# 4-20mA_Converter.net
KiCad netlist of a schematic drawn in Altium Designer
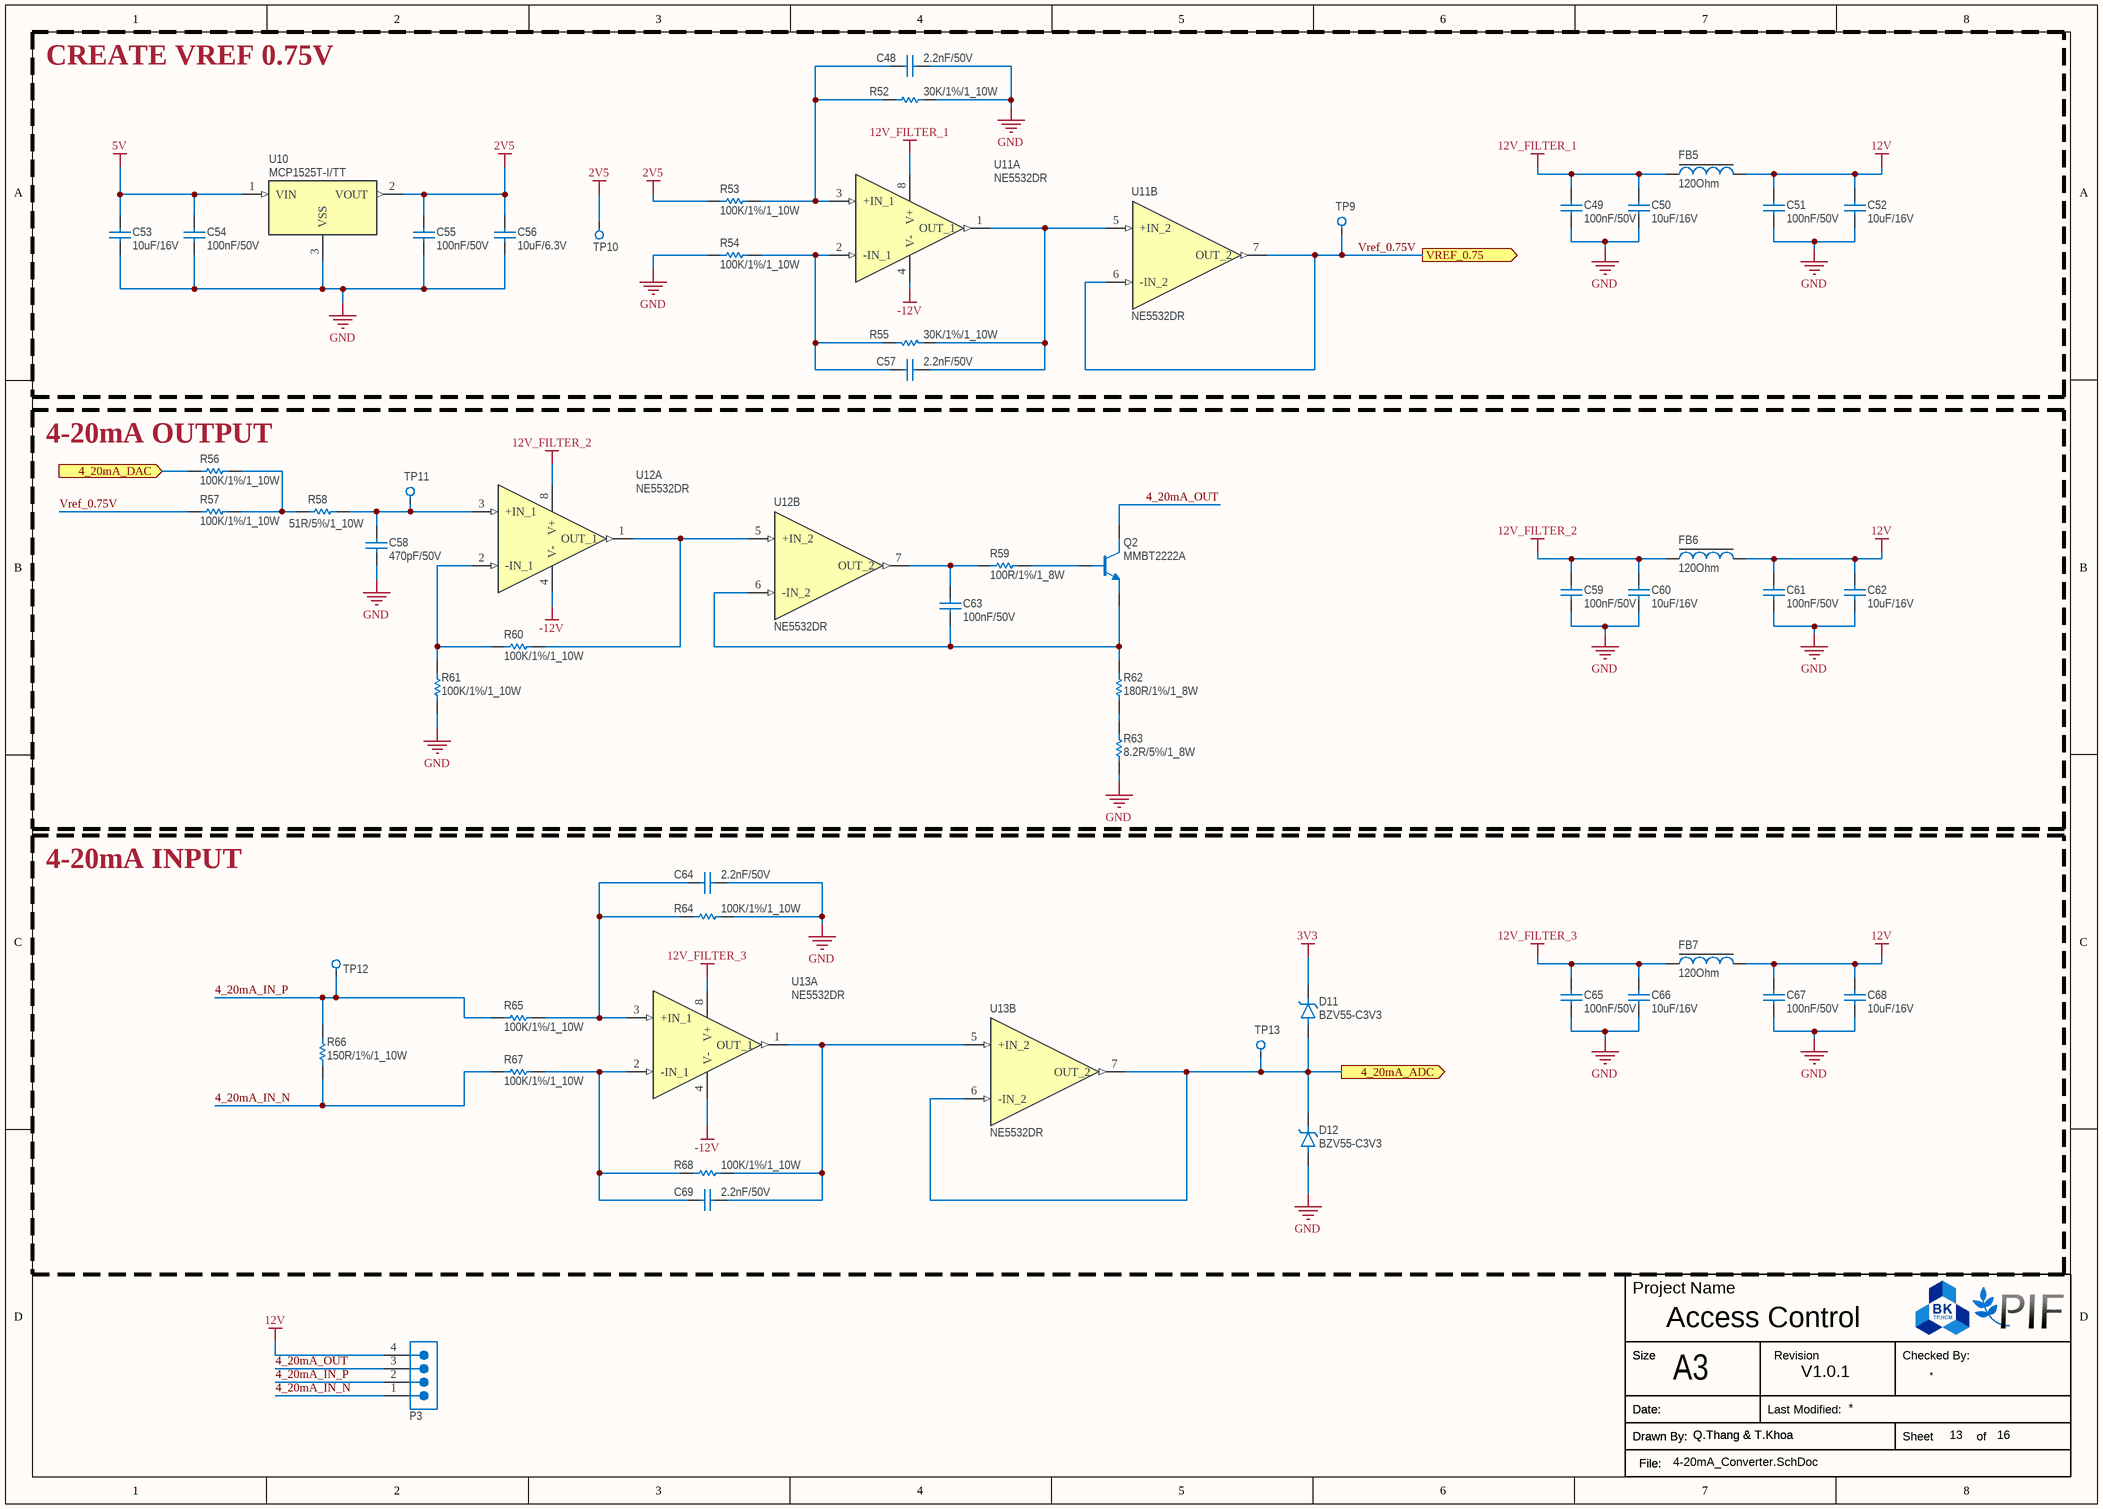
[diagram p0: 4-20mA_Converter.SchDoc]

(export (version "E")
  (design (tool "Eeschema 10.0.6"))
  (components
    (comp (ref "C48")
      (value "2.2nF/50V")
      (footprint "CAP_0603")
      (description "CAP, size 0603, 2.2nF, 50V")
      (fields (field (name "SUPPLY PART NUMBER") "CC0603KRX7R9BB222"))
      (libsource (lib "BluetoothTracking") (part "Ceramic_Cap_2.2nF_50V_0603"))
    )
    (comp (ref "C49")
      (value "100nF/50V")
      (footprint "CAP_0603")
      (description "CAP, size 0603, 100nF, 50V")
      (fields (field (name "SUPPLY PART NUMBER") "Tụ Gốm 0603 100nF (0.1uF) 50V"))
      (libsource (lib "BluetoothTracking") (part "Ceramic_Cap_100nF_50V_0603"))
    )
    (comp (ref "C50")
      (value "10uF/16V")
      (footprint "CAP_0603")
      (description "CAP, size 0603, 10uF, 16V")
      (fields (field (name "SUPPLY PART NUMBER") "Tụ Gốm 0603 10uF 16V"))
      (libsource (lib "BluetoothTracking") (part "Ceramic_Cap_10uF_16V_0603"))
    )
    (comp (ref "C51")
      (value "100nF/50V")
      (footprint "CAP_0603")
      (description "CAP, size 0603, 100nF, 50V")
      (fields (field (name "SUPPLY PART NUMBER") "Tụ Gốm 0603 100nF (0.1uF) 50V"))
      (libsource (lib "BluetoothTracking") (part "Ceramic_Cap_100nF_50V_0603"))
    )
    (comp (ref "C52")
      (value "10uF/16V")
      (footprint "CAP_0603")
      (description "CAP, size 0603, 10uF, 16V")
      (fields (field (name "SUPPLY PART NUMBER") "Tụ Gốm 0603 10uF 16V"))
      (libsource (lib "BluetoothTracking") (part "Ceramic_Cap_10uF_16V_0603"))
    )
    (comp (ref "C53")
      (value "10uF/16V")
      (footprint "CAP_0603")
      (description "CAP, size 0603, 10uF, 16V")
      (fields (field (name "SUPPLY PART NUMBER") "Tụ Gốm 0603 10uF 16V"))
      (libsource (lib "BluetoothTracking") (part "Ceramic_Cap_10uF_16V_0603"))
    )
    (comp (ref "C54")
      (value "100nF/50V")
      (footprint "CAP_0603")
      (description "CAP, size 0603, 100nF, 50V")
      (fields (field (name "SUPPLY PART NUMBER") "Tụ Gốm 0603 100nF (0.1uF) 50V"))
      (libsource (lib "BluetoothTracking") (part "Ceramic_Cap_100nF_50V_0603"))
    )
    (comp (ref "C55")
      (value "100nF/50V")
      (footprint "CAP_0603")
      (description "CAP, size 0603, 100nF, 50V")
      (fields (field (name "SUPPLY PART NUMBER") "Tụ Gốm 0603 100nF (0.1uF) 50V"))
      (libsource (lib "BluetoothTracking") (part "Ceramic_Cap_100nF_50V_0603"))
    )
    (comp (ref "C56")
      (value "10uF/6.3V")
      (footprint "CAP_0603")
      (description "CAP, size 0603, 10uF, 6.3V")
      (fields (field (name "SUPPLY PART NUMBER") "CC0603KRX5R5BB106"))
      (libsource (lib "BluetoothTracking") (part "Ceramic_Cap_10uF_6.3V_0603"))
    )
    (comp (ref "C57")
      (value "2.2nF/50V")
      (footprint "CAP_0603")
      (description "CAP, size 0603, 2.2nF, 50V")
      (fields (field (name "SUPPLY PART NUMBER") "CC0603KRX7R9BB222"))
      (libsource (lib "BluetoothTracking") (part "Ceramic_Cap_2.2nF_50V_0603"))
    )
    (comp (ref "C58")
      (value "470pF/50V")
      (footprint "CAP_0603")
      (description "CAP, size 0603, 470pF, 50V")
      (fields (field (name "SUPPLY PART NUMBER") "Tụ Gốm 0603 470pF 50V"))
      (libsource (lib "BluetoothTracking") (part "Ceramic_Cap_470pF_50V_0603"))
    )
    (comp (ref "C59")
      (value "100nF/50V")
      (footprint "CAP_0603")
      (description "CAP, size 0603, 100nF, 50V")
      (fields (field (name "SUPPLY PART NUMBER") "Tụ Gốm 0603 100nF (0.1uF) 50V"))
      (libsource (lib "BluetoothTracking") (part "Ceramic_Cap_100nF_50V_0603"))
    )
    (comp (ref "C60")
      (value "10uF/16V")
      (footprint "CAP_0603")
      (description "CAP, size 0603, 10uF, 16V")
      (fields (field (name "SUPPLY PART NUMBER") "Tụ Gốm 0603 10uF 16V"))
      (libsource (lib "BluetoothTracking") (part "Ceramic_Cap_10uF_16V_0603"))
    )
    (comp (ref "C61")
      (value "100nF/50V")
      (footprint "CAP_0603")
      (description "CAP, size 0603, 100nF, 50V")
      (fields (field (name "SUPPLY PART NUMBER") "Tụ Gốm 0603 100nF (0.1uF) 50V"))
      (libsource (lib "BluetoothTracking") (part "Ceramic_Cap_100nF_50V_0603"))
    )
    (comp (ref "C62")
      (value "10uF/16V")
      (footprint "CAP_0603")
      (description "CAP, size 0603, 10uF, 16V")
      (fields (field (name "SUPPLY PART NUMBER") "Tụ Gốm 0603 10uF 16V"))
      (libsource (lib "BluetoothTracking") (part "Ceramic_Cap_10uF_16V_0603"))
    )
    (comp (ref "C63")
      (value "100nF/50V")
      (footprint "CAP_0603")
      (description "CAP, size 0603, 100nF, 50V")
      (fields (field (name "SUPPLY PART NUMBER") "Tụ Gốm 0603 100nF (0.1uF) 50V"))
      (libsource (lib "BluetoothTracking") (part "Ceramic_Cap_100nF_50V_0603"))
    )
    (comp (ref "C64")
      (value "2.2nF/50V")
      (footprint "CAP_0603")
      (description "CAP, size 0603, 2.2nF, 50V")
      (fields (field (name "SUPPLY PART NUMBER") "CC0603KRX7R9BB222"))
      (libsource (lib "BluetoothTracking") (part "Ceramic_Cap_2.2nF_50V_0603"))
    )
    (comp (ref "C65")
      (value "100nF/50V")
      (footprint "CAP_0603")
      (description "CAP, size 0603, 100nF, 50V")
      (fields (field (name "SUPPLY PART NUMBER") "Tụ Gốm 0603 100nF (0.1uF) 50V"))
      (libsource (lib "BluetoothTracking") (part "Ceramic_Cap_100nF_50V_0603"))
    )
    (comp (ref "C66")
      (value "10uF/16V")
      (footprint "CAP_0603")
      (description "CAP, size 0603, 10uF, 16V")
      (fields (field (name "SUPPLY PART NUMBER") "Tụ Gốm 0603 10uF 16V"))
      (libsource (lib "BluetoothTracking") (part "Ceramic_Cap_10uF_16V_0603"))
    )
    (comp (ref "C67")
      (value "100nF/50V")
      (footprint "CAP_0603")
      (description "CAP, size 0603, 100nF, 50V")
      (fields (field (name "SUPPLY PART NUMBER") "Tụ Gốm 0603 100nF (0.1uF) 50V"))
      (libsource (lib "BluetoothTracking") (part "Ceramic_Cap_100nF_50V_0603"))
    )
    (comp (ref "C68")
      (value "10uF/16V")
      (footprint "CAP_0603")
      (description "CAP, size 0603, 10uF, 16V")
      (fields (field (name "SUPPLY PART NUMBER") "Tụ Gốm 0603 10uF 16V"))
      (libsource (lib "BluetoothTracking") (part "Ceramic_Cap_10uF_16V_0603"))
    )
    (comp (ref "C69")
      (value "2.2nF/50V")
      (footprint "CAP_0603")
      (description "CAP, size 0603, 2.2nF, 50V")
      (fields (field (name "SUPPLY PART NUMBER") "CC0603KRX7R9BB222"))
      (libsource (lib "BluetoothTracking") (part "Ceramic_Cap_2.2nF_50V_0603"))
    )
    (comp (ref "D11")
      (value "BZV55-C3V3")
      (footprint "SOD-80")
      (description "DIODE ZENER 3.3V 500 mW")
      (libsource (lib "BluetoothTracking") (part "Diode_BZV55C3V3"))
    )
    (comp (ref "D12")
      (value "BZV55-C3V3")
      (footprint "SOD-80")
      (description "DIODE ZENER 3.3V 500 mW")
      (libsource (lib "BluetoothTracking") (part "Diode_BZV55C3V3"))
    )
    (comp (ref "FB5")
      (value "120Ohm")
      (footprint "Ferrite_Bead_0805")
      (description "Ferrite Bead, size 0805, 120Ohm, 2A")
      (fields (field (name "SUPPLY PART NUMBER") "CBW201209U121T Ferrite Beads 2A 120 Ohm 0805"))
      (libsource (lib "BluetoothTracking") (part "Ferrite_Bead_120Ohm_2A_0805"))
    )
    (comp (ref "FB6")
      (value "120Ohm")
      (footprint "Ferrite_Bead_0805")
      (description "Ferrite Bead, size 0805, 120Ohm, 2A")
      (fields (field (name "SUPPLY PART NUMBER") "CBW201209U121T Ferrite Beads 2A 120 Ohm 0805"))
      (libsource (lib "BluetoothTracking") (part "Ferrite_Bead_120Ohm_2A_0805"))
    )
    (comp (ref "FB7")
      (value "120Ohm")
      (footprint "Ferrite_Bead_0805")
      (description "Ferrite Bead, size 0805, 120Ohm, 2A")
      (fields (field (name "SUPPLY PART NUMBER") "CBW201209U121T Ferrite Beads 2A 120 Ohm 0805"))
      (libsource (lib "BluetoothTracking") (part "Ferrite_Bead_120Ohm_2A_0805"))
    )
    (comp (ref "P3")
      (value "3.81mm_4P")
      (footprint "Terminal_Block_3.81mm_4P")
      (description "Terminal Block THT, pitch 3.81mm, 4p, 300V 10A")
      (fields
        (field (name "SUPPLY PART NUMBER") "UL-3.81-4-R Terminal Block Plug-in Hàn PCB 4 Chân Cong 3.81mm 300V 10A ULO")
      )
      (libsource (lib "BluetoothTracking") (part "Terminal_Block_3.81mm_4P"))
    )
    (comp (ref "Q2")
      (value "MMBT2222A")
      (footprint "SOT-23")
      (description "Điện áp Vce max: 40V, dòng Ic max: 0.6A, công suất: 0.3W")
      (fields (field (name "SUPPLY PART NUMBER") "MMBT2222A 1P Transistor NPN 40V 0.6A 3 Chân SOT-23"))
      (libsource (lib "BluetoothTracking") (part "MMBT2222A"))
    )
    (comp (ref "R52")
      (value "30K/1%/1_10W")
      (footprint "Resistor_0603")
      (description "Resistor 0603 30KOhm 1% 1_10W")
      (fields (field (name "SUPPLY PART NUMBER") "Điện Trở 30 KOhm 0603 1%"))
      (libsource (lib "BluetoothTracking") (part "Res_30K_0603_1%"))
    )
    (comp (ref "R53")
      (value "100K/1%/1_10W")
      (footprint "Resistor_0603")
      (description "Resistor 0603 100KOhm 1% 1_10W")
      (fields (field (name "SUPPLY PART NUMBER") "Điện Trở 100 KOhm 0603 1%"))
      (libsource (lib "BluetoothTracking") (part "Res_100K_0603_1%"))
    )
    (comp (ref "R54")
      (value "100K/1%/1_10W")
      (footprint "Resistor_0603")
      (description "Resistor 0603 100KOhm 1% 1_10W")
      (fields (field (name "SUPPLY PART NUMBER") "Điện Trở 100 KOhm 0603 1%"))
      (libsource (lib "BluetoothTracking") (part "Res_100K_0603_1%"))
    )
    (comp (ref "R55")
      (value "30K/1%/1_10W")
      (footprint "Resistor_0603")
      (description "Resistor 0603 30KOhm 1% 1_10W")
      (fields (field (name "SUPPLY PART NUMBER") "Điện Trở 30 KOhm 0603 1%"))
      (libsource (lib "BluetoothTracking") (part "Res_30K_0603_1%"))
    )
    (comp (ref "R56")
      (value "100K/1%/1_10W")
      (footprint "Resistor_0603")
      (description "Resistor 0603 100KOhm 1% 1_10W")
      (fields (field (name "SUPPLY PART NUMBER") "Điện Trở 100 KOhm 0603 1%"))
      (libsource (lib "BluetoothTracking") (part "Res_100K_0603_1%"))
    )
    (comp (ref "R57")
      (value "100K/1%/1_10W")
      (footprint "Resistor_0603")
      (description "Resistor 0603 100KOhm 1% 1_10W")
      (fields (field (name "SUPPLY PART NUMBER") "Điện Trở 100 KOhm 0603 1%"))
      (libsource (lib "BluetoothTracking") (part "Res_100K_0603_1%"))
    )
    (comp (ref "R58")
      (value "51R/5%/1_10W")
      (footprint "Resistor_0603")
      (description "Resistor 0603 51 Ohm 5% 1_10W")
      (fields (field (name "SUPPLY PART NUMBER") "Điện Trở 51 Ohm 0603 5%"))
      (libsource (lib "BluetoothTracking") (part "Res_51R_0603_5%"))
    )
    (comp (ref "R59")
      (value "100R/1%/1_8W")
      (footprint "Resistor_0603")
      (description "Resistor 0805 100 Ohm 1% 1_8W")
      (fields (field (name "SUPPLY PART NUMBER") "Điện Trở 100 Ohm 0805 1%"))
      (libsource (lib "BluetoothTracking") (part "Res_100R_0805_1%"))
    )
    (comp (ref "R60")
      (value "100K/1%/1_10W")
      (footprint "Resistor_0603")
      (description "Resistor 0603 100KOhm 1% 1_10W")
      (fields (field (name "SUPPLY PART NUMBER") "Điện Trở 100 KOhm 0603 1%"))
      (libsource (lib "BluetoothTracking") (part "Res_100K_0603_1%"))
    )
    (comp (ref "R61")
      (value "100K/1%/1_10W")
      (footprint "Resistor_0603")
      (description "Resistor 0603 100KOhm 1% 1_10W")
      (fields (field (name "SUPPLY PART NUMBER") "Điện Trở 100 KOhm 0603 1%"))
      (libsource (lib "BluetoothTracking") (part "Res_100K_0603_1%"))
    )
    (comp (ref "R62")
      (value "180R/1%/1_8W")
      (footprint "Resistor_0805")
      (description "Resistor 0805 180 Ohm 1% 1_8W")
      (fields (field (name "SUPPLY PART NUMBER") "Điện Trở 180 Ohm 0805 1%"))
      (libsource (lib "BluetoothTracking") (part "Res_180R_0805_1%"))
    )
    (comp (ref "R63")
      (value "8.2R/5%/1_8W")
      (footprint "Resistor_0805")
      (description "Resistor 0805 8.2 Ohm 5% 1_8W")
      (fields (field (name "SUPPLY PART NUMBER") "Điện Trở 8.2 Ohm 0805 5%"))
      (libsource (lib "BluetoothTracking") (part "Res_8.2R_0805_5%"))
    )
    (comp (ref "R64")
      (value "100K/1%/1_10W")
      (footprint "Resistor_0603")
      (description "Resistor 0603 100KOhm 1% 1_10W")
      (fields (field (name "SUPPLY PART NUMBER") "Điện Trở 100 KOhm 0603 1%"))
      (libsource (lib "BluetoothTracking") (part "Res_100K_0603_1%"))
    )
    (comp (ref "R65")
      (value "100K/1%/1_10W")
      (footprint "Resistor_0603")
      (description "Resistor 0603 100KOhm 1% 1_10W")
      (fields (field (name "SUPPLY PART NUMBER") "Điện Trở 100 KOhm 0603 1%"))
      (libsource (lib "BluetoothTracking") (part "Res_100K_0603_1%"))
    )
    (comp (ref "R66")
      (value "150R/1%/1_10W")
      (footprint "Resistor_0603")
      (description "Resistor 0603 150 Ohm 1% 1_10W")
      (fields (field (name "SUPPLY PART NUMBER") "Điện Trở 150 Ohm 0603 1%"))
      (libsource (lib "BluetoothTracking") (part "Res_150R_0603_1%"))
    )
    (comp (ref "R67")
      (value "100K/1%/1_10W")
      (footprint "Resistor_0603")
      (description "Resistor 0603 100KOhm 1% 1_10W")
      (fields (field (name "SUPPLY PART NUMBER") "Điện Trở 100 KOhm 0603 1%"))
      (libsource (lib "BluetoothTracking") (part "Res_100K_0603_1%"))
    )
    (comp (ref "R68")
      (value "100K/1%/1_10W")
      (footprint "Resistor_0603")
      (description "Resistor 0603 100KOhm 1% 1_10W")
      (fields (field (name "SUPPLY PART NUMBER") "Điện Trở 100 KOhm 0603 1%"))
      (libsource (lib "BluetoothTracking") (part "Res_100K_0603_1%"))
    )
    (comp (ref "TP9")
      (value "VREF_0.75V")
      (footprint "TestPoint_Pad_3.0x3.0mm")
      (libsource (lib "BluetoothTracking") (part "Testpoint_SMD"))
    )
    (comp (ref "TP10")
      (value "2V5")
      (footprint "TestPoint_Pad_3.0x3.0mm")
      (libsource (lib "BluetoothTracking") (part "Testpoint_SMD"))
    )
    (comp (ref "TP11")
      (value "4-20mA_DAC")
      (footprint "TestPoint_THTPad_D1.5mm_Drill0.7mm")
      (description "Test Point TEST-1BK")
      (libsource (lib "BluetoothTracking") (part "Testpoint_TH"))
    )
    (comp (ref "TP12")
      (value "4_20mA_IN")
      (footprint "TestPoint_THTPad_D1.5mm_Drill0.7mm")
      (description "Test Point TEST-1BK")
      (libsource (lib "BluetoothTracking") (part "Testpoint_TH"))
    )
    (comp (ref "TP13")
      (value "4-20mA_ADC")
      (footprint "TestPoint_THTPad_D1.5mm_Drill0.7mm")
      (description "Test Point TEST-1BK")
      (libsource (lib "BluetoothTracking") (part "Testpoint_TH"))
    )
    (comp (ref "U10")
      (value "MCP1525T-I/TT")
      (footprint "SOT-23")
      (description "Voltage Reference IC 2.5V")
      (fields (field (name "SUPPLY PART NUMBER") "MCP1525T-I/TT IC Tham Chiếu Điện Áp 2.5V SOT-23"))
      (libsource (lib "BluetoothTracking") (part "MCP1525T-I/TT"))
    )
    (comp (ref "U11")
      (value "NE5532DR")
      (footprint "SOIC-8")
      (description "Low Noise Single/Dual Operational Amplifier - SOIC-8")
      (libsource (lib "BluetoothTracking") (part "NE5532DR"))
    )
    (comp (ref "U12")
      (value "NE5532DR")
      (footprint "SOIC-8")
      (description "Low Noise Single/Dual Operational Amplifier - SOIC-8")
      (libsource (lib "BluetoothTracking") (part "NE5532DR"))
    )
    (comp (ref "U13")
      (value "NE5532DR")
      (footprint "SOIC-8")
      (description "Low Noise Single/Dual Operational Amplifier - SOIC-8")
      (libsource (lib "BluetoothTracking") (part "NE5532DR"))
    )
  )
  (nets
    (net (code "1") (name "-12V") (class "Default")
      (node (ref "U11") (pin "4") (pinfunction "V-_4") (pintype "power_in"))
      (node (ref "U12") (pin "4") (pinfunction "V-_4") (pintype "power_in"))
      (node (ref "U13") (pin "4") (pinfunction "V-_4") (pintype "power_in"))
    )
    (net (code "2") (name "/4_20mA_ADC") (class "Default")
      (node (ref "D11") (pin "A") (pinfunction "A_A") (pintype "passive"))
      (node (ref "D12") (pin "C") (pinfunction "C_C") (pintype "passive"))
      (node (ref "TP13") (pin "1") (pinfunction "1_1") (pintype "passive"))
      (node (ref "U13") (pin "6") (pinfunction "-IN_2_6") (pintype "input"))
      (node (ref "U13") (pin "7") (pinfunction "OUT_2_7") (pintype "output"))
    )
    (net (code "3") (name "/4_20mA_DAC") (class "Default")
      (node (ref "R56") (pin "1") (pinfunction "1_1") (pintype "passive"))
    )
    (net (code "4") (name "/4_20mA_IN_N") (class "Default")
      (node (ref "P3") (pin "1") (pinfunction "1_1") (pintype "passive"))
      (node (ref "R66") (pin "1") (pinfunction "1_1") (pintype "passive"))
      (node (ref "R67") (pin "1") (pinfunction "1_1") (pintype "passive"))
    )
    (net (code "5") (name "/4_20mA_IN_P") (class "Default")
      (node (ref "P3") (pin "2") (pinfunction "2_2") (pintype "passive"))
      (node (ref "R65") (pin "1") (pinfunction "1_1") (pintype "passive"))
      (node (ref "R66") (pin "2") (pinfunction "2_2") (pintype "passive"))
      (node (ref "TP12") (pin "1") (pinfunction "1_1") (pintype "passive"))
    )
    (net (code "6") (name "/4_20mA_OUT") (class "Default")
      (node (ref "P3") (pin "3") (pinfunction "3_3") (pintype "passive"))
      (node (ref "Q2") (pin "3") (pinfunction "C_3") (pintype "passive"))
    )
    (net (code "7") (name "/Vref_0.75V") (class "Default")
      (node (ref "R57") (pin "1") (pinfunction "1_1") (pintype "passive"))
      (node (ref "TP9") (pin "1") (pinfunction "1_1") (pintype "passive"))
      (node (ref "U11") (pin "6") (pinfunction "-IN_2_6") (pintype "input"))
      (node (ref "U11") (pin "7") (pinfunction "OUT_2_7") (pintype "output"))
    )
    (net (code "8") (name "2V5") (class "Default")
      (node (ref "C55") (pin "2") (pinfunction "2_2") (pintype "passive"))
      (node (ref "C56") (pin "2") (pinfunction "2_2") (pintype "passive"))
      (node (ref "R53") (pin "1") (pinfunction "1_1") (pintype "passive"))
      (node (ref "TP10") (pin "1") (pinfunction "1_1") (pintype "passive"))
      (node (ref "U10") (pin "2") (pinfunction "VOUT_2") (pintype "output"))
    )
    (net (code "9") (name "3V3") (class "Default")
      (node (ref "D11") (pin "C") (pinfunction "C_C") (pintype "passive"))
    )
    (net (code "10") (name "5V") (class "Default")
      (node (ref "C53") (pin "2") (pinfunction "2_2") (pintype "passive"))
      (node (ref "C54") (pin "2") (pinfunction "2_2") (pintype "passive"))
      (node (ref "U10") (pin "1") (pinfunction "VIN_1") (pintype "input"))
    )
    (net (code "11") (name "12V") (class "Default")
      (node (ref "C51") (pin "2") (pinfunction "2_2") (pintype "passive"))
      (node (ref "C52") (pin "2") (pinfunction "2_2") (pintype "passive"))
      (node (ref "C61") (pin "2") (pinfunction "2_2") (pintype "passive"))
      (node (ref "C62") (pin "2") (pinfunction "2_2") (pintype "passive"))
      (node (ref "C67") (pin "2") (pinfunction "2_2") (pintype "passive"))
      (node (ref "C68") (pin "2") (pinfunction "2_2") (pintype "passive"))
      (node (ref "FB5") (pin "2") (pinfunction "2_2") (pintype "passive"))
      (node (ref "FB6") (pin "2") (pinfunction "2_2") (pintype "passive"))
      (node (ref "FB7") (pin "2") (pinfunction "2_2") (pintype "passive"))
      (node (ref "P3") (pin "4") (pinfunction "4_4") (pintype "passive"))
    )
    (net (code "12") (name "12V_FILTER_1") (class "Default")
      (node (ref "C49") (pin "2") (pinfunction "2_2") (pintype "passive"))
      (node (ref "C50") (pin "2") (pinfunction "2_2") (pintype "passive"))
      (node (ref "FB5") (pin "1") (pinfunction "1_1") (pintype "passive"))
      (node (ref "U11") (pin "8") (pinfunction "V+_8") (pintype "power_in"))
    )
    (net (code "13") (name "12V_FILTER_2") (class "Default")
      (node (ref "C59") (pin "2") (pinfunction "2_2") (pintype "passive"))
      (node (ref "C60") (pin "2") (pinfunction "2_2") (pintype "passive"))
      (node (ref "FB6") (pin "1") (pinfunction "1_1") (pintype "passive"))
      (node (ref "U12") (pin "8") (pinfunction "V+_8") (pintype "power_in"))
    )
    (net (code "14") (name "12V_FILTER_3") (class "Default")
      (node (ref "C65") (pin "2") (pinfunction "2_2") (pintype "passive"))
      (node (ref "C66") (pin "2") (pinfunction "2_2") (pintype "passive"))
      (node (ref "FB7") (pin "1") (pinfunction "1_1") (pintype "passive"))
      (node (ref "U13") (pin "8") (pinfunction "V+_8") (pintype "power_in"))
    )
    (net (code "15") (name "GND") (class "Default")
      (node (ref "C48") (pin "2") (pinfunction "2_2") (pintype "passive"))
      (node (ref "C49") (pin "1") (pinfunction "1_1") (pintype "passive"))
      (node (ref "C50") (pin "1") (pinfunction "1_1") (pintype "passive"))
      (node (ref "C51") (pin "1") (pinfunction "1_1") (pintype "passive"))
      (node (ref "C52") (pin "1") (pinfunction "1_1") (pintype "passive"))
      (node (ref "C53") (pin "1") (pinfunction "1_1") (pintype "passive"))
      (node (ref "C54") (pin "1") (pinfunction "1_1") (pintype "passive"))
      (node (ref "C55") (pin "1") (pinfunction "1_1") (pintype "passive"))
      (node (ref "C56") (pin "1") (pinfunction "1_1") (pintype "passive"))
      (node (ref "C58") (pin "1") (pinfunction "1_1") (pintype "passive"))
      (node (ref "C59") (pin "1") (pinfunction "1_1") (pintype "passive"))
      (node (ref "C60") (pin "1") (pinfunction "1_1") (pintype "passive"))
      (node (ref "C61") (pin "1") (pinfunction "1_1") (pintype "passive"))
      (node (ref "C62") (pin "1") (pinfunction "1_1") (pintype "passive"))
      (node (ref "C64") (pin "2") (pinfunction "2_2") (pintype "passive"))
      (node (ref "C65") (pin "1") (pinfunction "1_1") (pintype "passive"))
      (node (ref "C66") (pin "1") (pinfunction "1_1") (pintype "passive"))
      (node (ref "C67") (pin "1") (pinfunction "1_1") (pintype "passive"))
      (node (ref "C68") (pin "1") (pinfunction "1_1") (pintype "passive"))
      (node (ref "D12") (pin "A") (pinfunction "A_A") (pintype "passive"))
      (node (ref "R52") (pin "2") (pinfunction "2_2") (pintype "passive"))
      (node (ref "R54") (pin "1") (pinfunction "1_1") (pintype "passive"))
      (node (ref "R61") (pin "1") (pinfunction "1_1") (pintype "passive"))
      (node (ref "R63") (pin "2") (pinfunction "2_2") (pintype "passive"))
      (node (ref "R64") (pin "2") (pinfunction "2_2") (pintype "passive"))
      (node (ref "U10") (pin "3") (pinfunction "VSS_3") (pintype "passive"))
    )
    (net (code "16") (name "Net-(Q2-B)") (class "Default")
      (node (ref "Q2") (pin "1") (pinfunction "B_1") (pintype "passive"))
      (node (ref "R59") (pin "2") (pinfunction "2_2") (pintype "passive"))
    )
    (net (code "17") (name "Net-(Q2-E)") (class "Default")
      (node (ref "C63") (pin "1") (pinfunction "1_1") (pintype "passive"))
      (node (ref "Q2") (pin "2") (pinfunction "E_2") (pintype "passive"))
      (node (ref "R62") (pin "2") (pinfunction "2_2") (pintype "passive"))
      (node (ref "U12") (pin "6") (pinfunction "-IN_2_6") (pintype "input"))
    )
    (net (code "18") (name "Net-(R56-Pad2)") (class "Default")
      (node (ref "R56") (pin "2") (pinfunction "2_2") (pintype "passive"))
      (node (ref "R57") (pin "2") (pinfunction "2_2") (pintype "passive"))
      (node (ref "R58") (pin "1") (pinfunction "1_1") (pintype "passive"))
    )
    (net (code "19") (name "Net-(R62-Pad1)") (class "Default")
      (node (ref "R62") (pin "1") (pinfunction "1_1") (pintype "passive"))
      (node (ref "R63") (pin "1") (pinfunction "1_1") (pintype "passive"))
    )
    (net (code "20") (name "Net-(U11A-+IN_1)") (class "Default")
      (node (ref "C48") (pin "1") (pinfunction "1_1") (pintype "passive"))
      (node (ref "R52") (pin "1") (pinfunction "1_1") (pintype "passive"))
      (node (ref "R53") (pin "2") (pinfunction "2_2") (pintype "passive"))
      (node (ref "U11") (pin "3") (pinfunction "+IN_1_3") (pintype "input"))
    )
    (net (code "21") (name "Net-(U11A--IN_1)") (class "Default")
      (node (ref "C57") (pin "1") (pinfunction "1_1") (pintype "passive"))
      (node (ref "R54") (pin "2") (pinfunction "2_2") (pintype "passive"))
      (node (ref "R55") (pin "1") (pinfunction "1_1") (pintype "passive"))
      (node (ref "U11") (pin "2") (pinfunction "-IN_1_2") (pintype "input"))
    )
    (net (code "22") (name "Net-(U11A-OUT_1)") (class "Default")
      (node (ref "C57") (pin "2") (pinfunction "2_2") (pintype "passive"))
      (node (ref "R55") (pin "2") (pinfunction "2_2") (pintype "passive"))
      (node (ref "U11") (pin "1") (pinfunction "OUT_1_1") (pintype "output"))
      (node (ref "U11") (pin "5") (pinfunction "+IN_2_5") (pintype "input"))
    )
    (net (code "23") (name "Net-(U12A-+IN_1)") (class "Default")
      (node (ref "C58") (pin "2") (pinfunction "2_2") (pintype "passive"))
      (node (ref "R58") (pin "2") (pinfunction "2_2") (pintype "passive"))
      (node (ref "TP11") (pin "1") (pinfunction "1_1") (pintype "passive"))
      (node (ref "U12") (pin "3") (pinfunction "+IN_1_3") (pintype "input"))
    )
    (net (code "24") (name "Net-(U12A--IN_1)") (class "Default")
      (node (ref "R60") (pin "1") (pinfunction "1_1") (pintype "passive"))
      (node (ref "R61") (pin "2") (pinfunction "2_2") (pintype "passive"))
      (node (ref "U12") (pin "2") (pinfunction "-IN_1_2") (pintype "input"))
    )
    (net (code "25") (name "Net-(U12A-OUT_1)") (class "Default")
      (node (ref "R60") (pin "2") (pinfunction "2_2") (pintype "passive"))
      (node (ref "U12") (pin "1") (pinfunction "OUT_1_1") (pintype "output"))
      (node (ref "U12") (pin "5") (pinfunction "+IN_2_5") (pintype "input"))
    )
    (net (code "26") (name "Net-(U12B-OUT_2)") (class "Default")
      (node (ref "C63") (pin "2") (pinfunction "2_2") (pintype "passive"))
      (node (ref "R59") (pin "1") (pinfunction "1_1") (pintype "passive"))
      (node (ref "U12") (pin "7") (pinfunction "OUT_2_7") (pintype "output"))
    )
    (net (code "27") (name "Net-(U13A-+IN_1)") (class "Default")
      (node (ref "C64") (pin "1") (pinfunction "1_1") (pintype "passive"))
      (node (ref "R64") (pin "1") (pinfunction "1_1") (pintype "passive"))
      (node (ref "R65") (pin "2") (pinfunction "2_2") (pintype "passive"))
      (node (ref "U13") (pin "3") (pinfunction "+IN_1_3") (pintype "input"))
    )
    (net (code "28") (name "Net-(U13A--IN_1)") (class "Default")
      (node (ref "C69") (pin "1") (pinfunction "1_1") (pintype "passive"))
      (node (ref "R67") (pin "2") (pinfunction "2_2") (pintype "passive"))
      (node (ref "R68") (pin "1") (pinfunction "1_1") (pintype "passive"))
      (node (ref "U13") (pin "2") (pinfunction "-IN_1_2") (pintype "input"))
    )
    (net (code "29") (name "Net-(U13A-OUT_1)") (class "Default")
      (node (ref "C69") (pin "2") (pinfunction "2_2") (pintype "passive"))
      (node (ref "R68") (pin "2") (pinfunction "2_2") (pintype "passive"))
      (node (ref "U13") (pin "1") (pinfunction "OUT_1_1") (pintype "output"))
      (node (ref "U13") (pin "5") (pinfunction "+IN_2_5") (pintype "input"))
    )
  )
)
